# attiny85.net
KiCad netlist of a schematic drawn in EAGLE
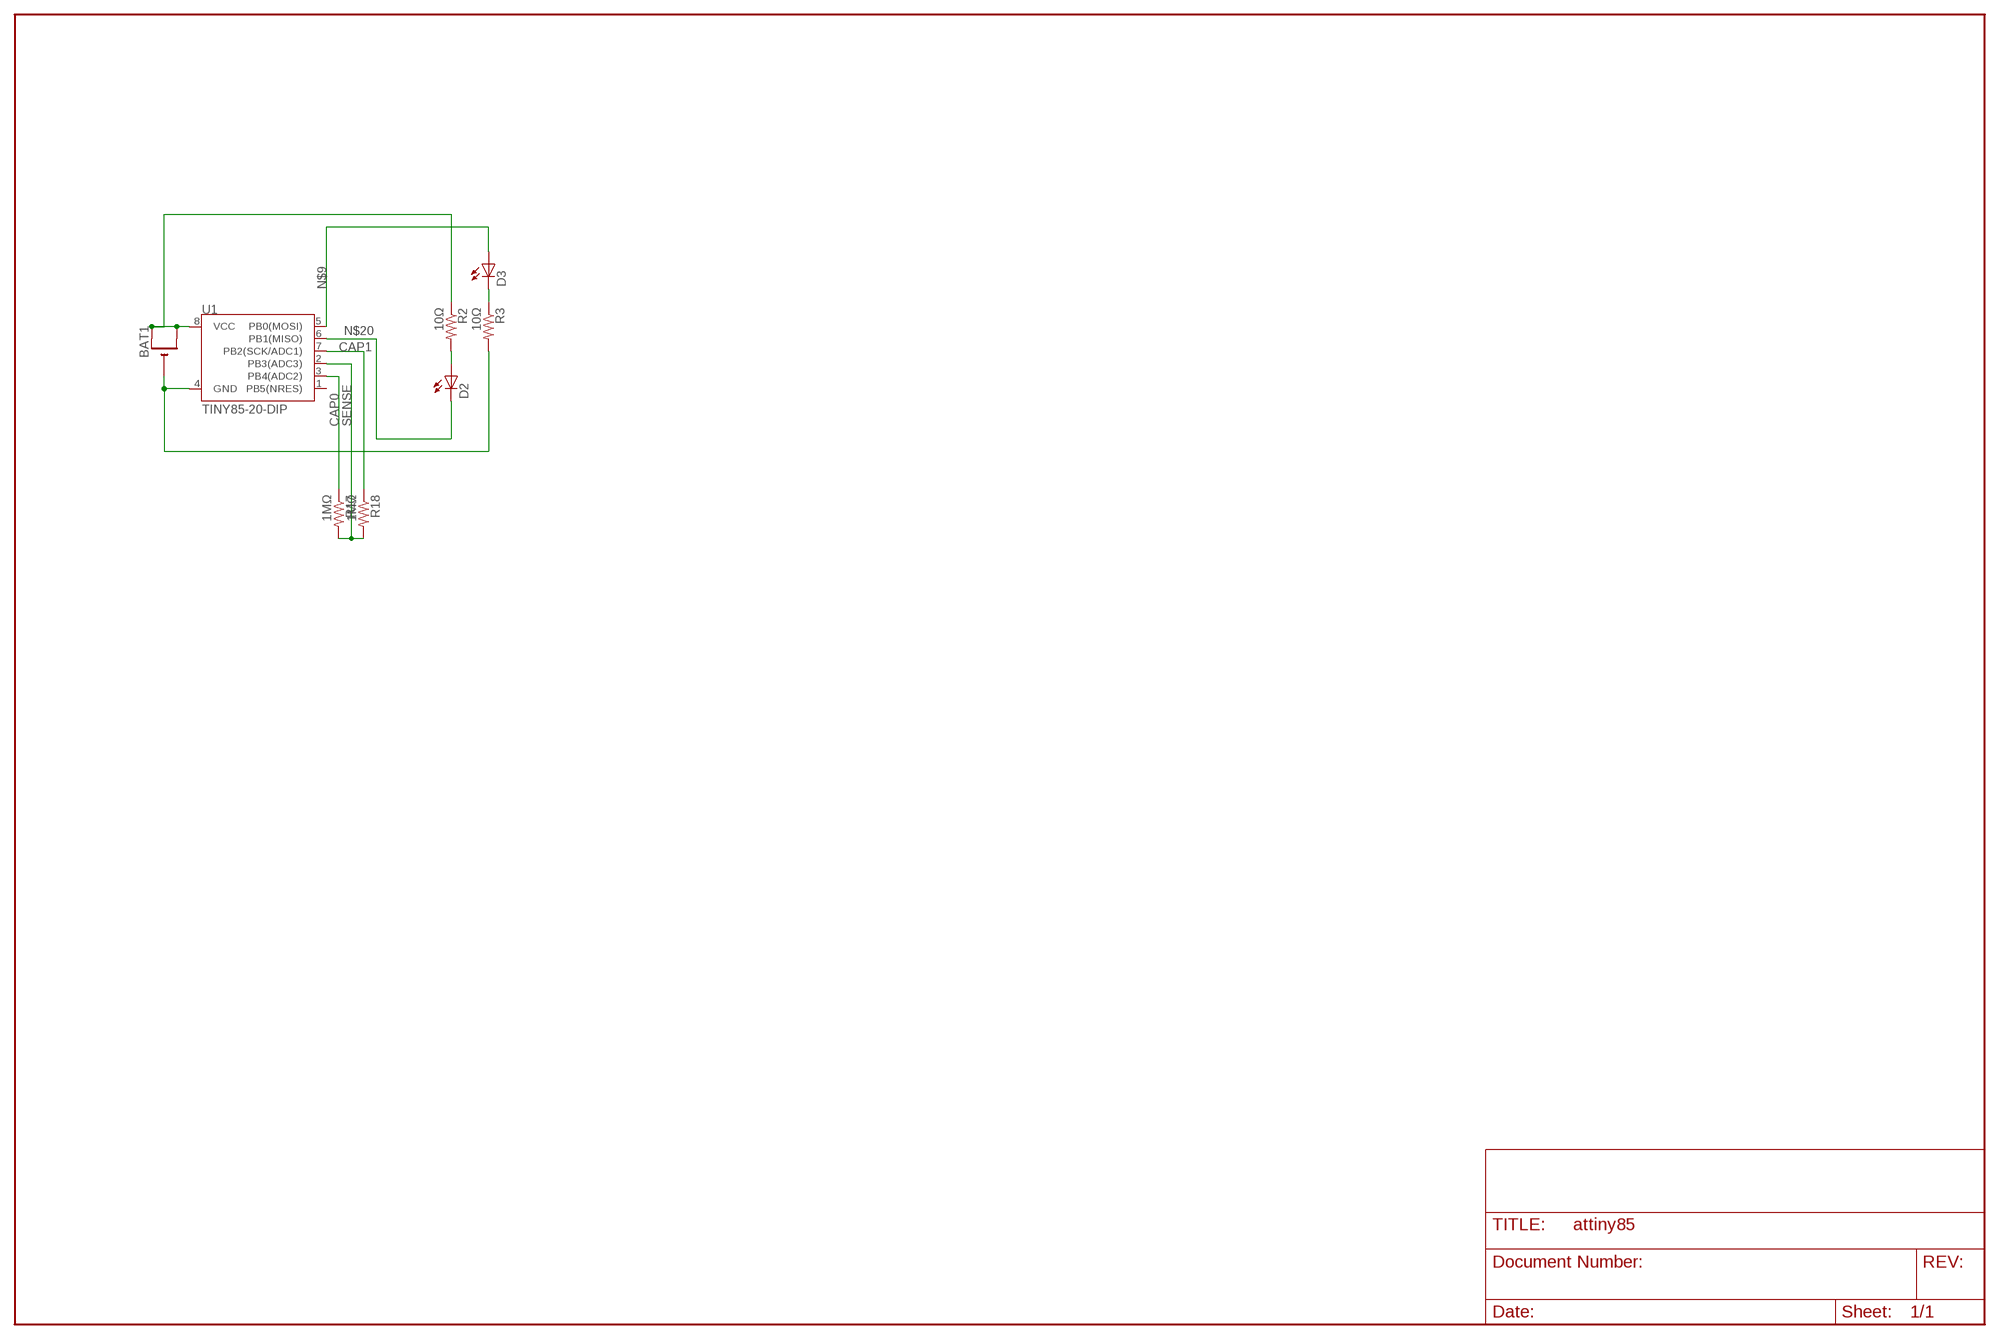
[diagram p0: schematic, sheet 1]

(export (version "E")
  (design (tool "Eeschema 10.0.6"))
  (components
    (comp (ref "BAT1")
      (value "CR2032THM")
      (footprint "eagle-import:CR2032-THRU")
      (libsource (lib "eagle-import") (part "CR2032THM"))
    )
    (comp (ref "D2")
      (value "LED5MM")
      (footprint "eagle-import:LED5MM")
      (libsource (lib "eagle-import") (part "LED5MM"))
    )
    (comp (ref "D3")
      (value "LED5MM")
      (footprint "eagle-import:LED5MM")
      (libsource (lib "eagle-import") (part "LED5MM"))
    )
    (comp (ref "R2")
      (value "10Ω")
      (footprint "eagle-import:AXIAL-0.3")
      (libsource (lib "eagle-import") (part "1KOHM-1/4W-5%(PTH)"))
    )
    (comp (ref "R3")
      (value "10Ω")
      (footprint "eagle-import:AXIAL-0.3")
      (libsource (lib "eagle-import") (part "1KOHM-1/4W-5%(PTH)"))
    )
    (comp (ref "R17")
      (value "1MΩ")
      (footprint "eagle-import:AXIAL-0.3")
      (libsource (lib "eagle-import") (part "1KOHM-1/4W-5%(PTH)"))
    )
    (comp (ref "R18")
      (value "1MΩ")
      (footprint "eagle-import:AXIAL-0.3")
      (libsource (lib "eagle-import") (part "1KOHM-1/4W-5%(PTH)"))
    )
    (comp (ref "U1")
      (value "TINY85-20-DIP")
      (footprint "eagle-import:DIP08")
      (libsource (lib "eagle-import") (part "ATTINY45TINY85-20-DIP"))
    )
  )
  (nets
    (net (code "1") (name "/CAP0") (class "Default")
      (node (ref "R17") (pin "P$1") (pinfunction "1_P$1") (pintype "passive"))
      (node (ref "U1") (pin "3") (pinfunction "PB4(ADC2)_3") (pintype "bidirectional"))
    )
    (net (code "2") (name "/CAP1") (class "Default")
      (node (ref "R18") (pin "P$1") (pinfunction "1_P$1") (pintype "passive"))
      (node (ref "U1") (pin "7") (pinfunction "PB2(SCK/ADC1)_7") (pintype "bidirectional"))
    )
    (net (code "3") (name "/N$9") (class "Default")
      (node (ref "D3") (pin "A") (pinfunction "A_A") (pintype "passive"))
      (node (ref "U1") (pin "5") (pinfunction "PB0(MOSI)_5") (pintype "bidirectional"))
    )
    (net (code "4") (name "/N$20") (class "Default")
      (node (ref "D2") (pin "K") (pinfunction "C_K") (pintype "passive"))
      (node (ref "U1") (pin "6") (pinfunction "PB1(MISO)_6") (pintype "bidirectional"))
    )
    (net (code "5") (name "/SENSE") (class "Default")
      (node (ref "R17") (pin "P$2") (pinfunction "2_P$2") (pintype "passive"))
      (node (ref "R18") (pin "P$2") (pinfunction "2_P$2") (pintype "passive"))
      (node (ref "U1") (pin "2") (pinfunction "PB3(ADC3)_2") (pintype "bidirectional"))
    )
    (net (code "6") (name "Net-(BAT1-+)") (class "Default")
      (node (ref "BAT1") (pin "+1") (pinfunction "+_+1") (pintype "passive"))
      (node (ref "BAT1") (pin "+2") (pinfunction "+1_+2") (pintype "passive"))
      (node (ref "R2") (pin "P$1") (pinfunction "1_P$1") (pintype "passive"))
      (node (ref "U1") (pin "8") (pinfunction "VCC_8") (pintype "bidirectional"))
    )
    (net (code "7") (name "Net-(D3-C)") (class "Default")
      (node (ref "D3") (pin "K") (pinfunction "C_K") (pintype "passive"))
      (node (ref "R3") (pin "P$1") (pinfunction "1_P$1") (pintype "passive"))
    )
    (net (code "8") (name "Net-(R2-2)") (class "Default")
      (node (ref "D2") (pin "A") (pinfunction "A_A") (pintype "passive"))
      (node (ref "R2") (pin "P$2") (pinfunction "2_P$2") (pintype "passive"))
    )
    (net (code "9") (name "Net-(R3-2)") (class "Default")
      (node (ref "BAT1") (pin "-") (pinfunction "-_-") (pintype "passive"))
      (node (ref "R3") (pin "P$2") (pinfunction "2_P$2") (pintype "passive"))
      (node (ref "U1") (pin "4") (pinfunction "GND_4") (pintype "bidirectional"))
    )
    (net (code "10") (name "unconnected-(U1-PB5(NRES)-Pad1)") (class "Default")
      (node (ref "U1") (pin "1") (pinfunction "PB5(NRES)_1") (pintype "bidirectional"))
    )
  )
)
